# PWR_Stage.net
KiCad netlist of a schematic drawn in Altium Designer
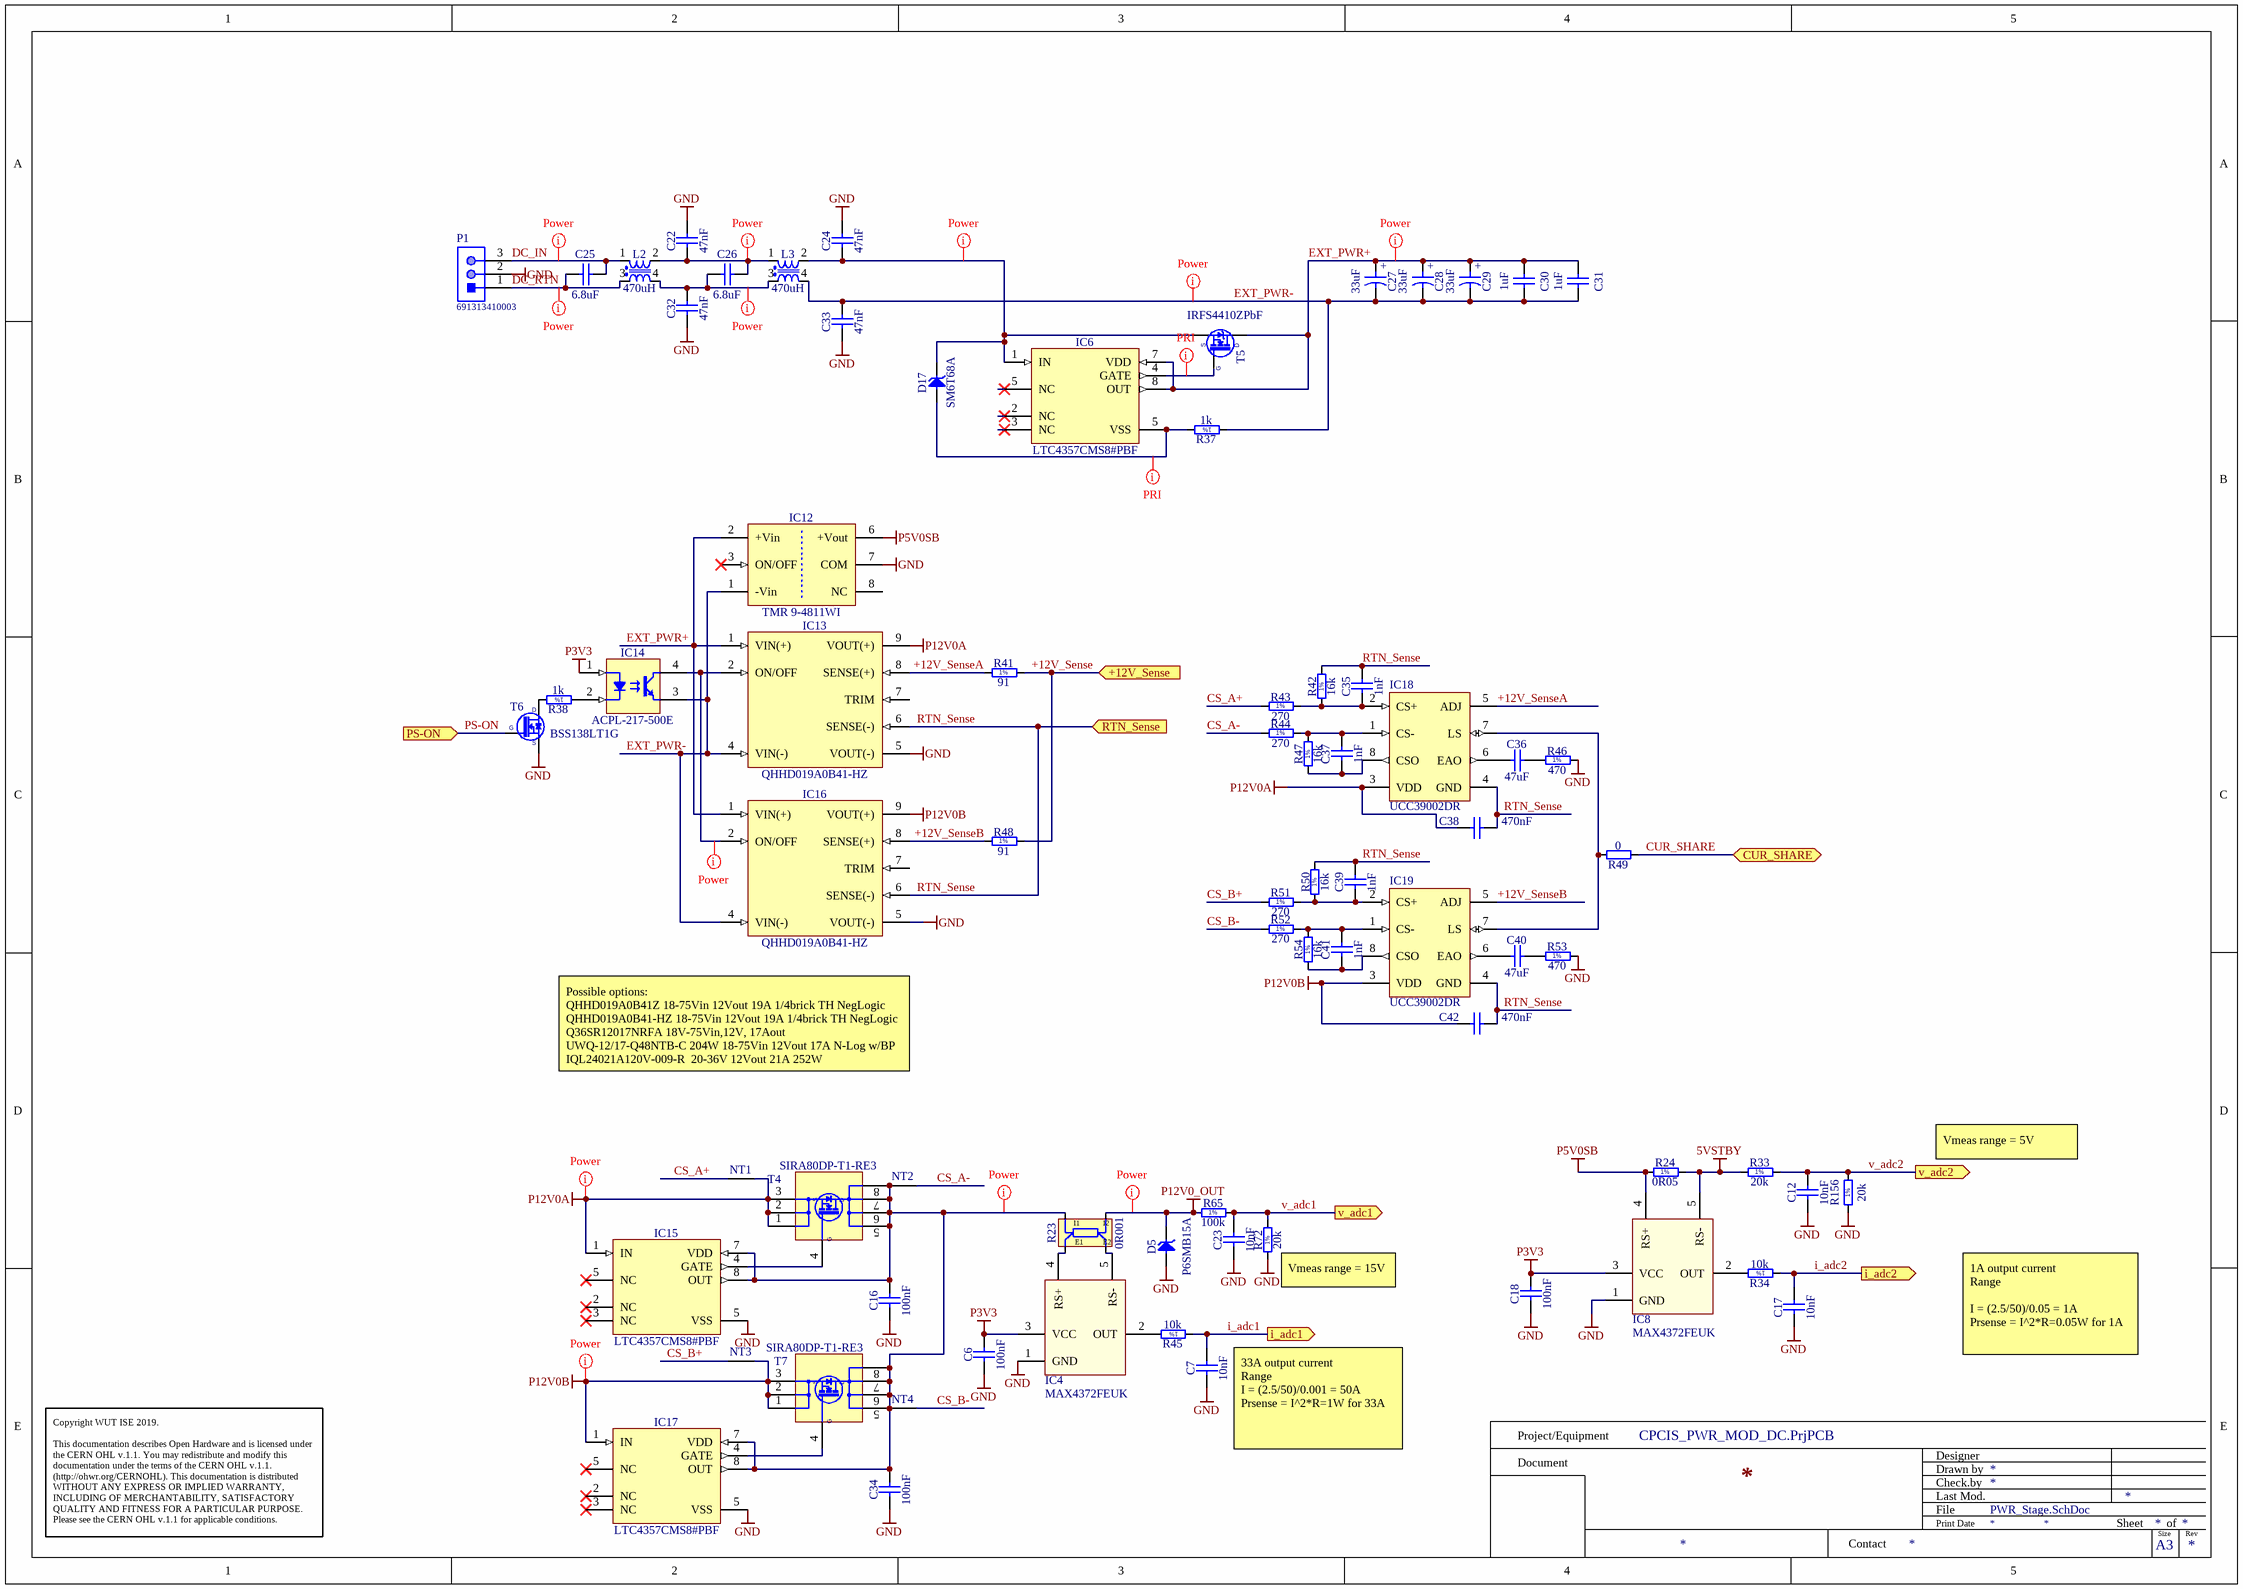
[diagram p0: PWR_Stage.SchDoc]

(export (version "E")
  (design (tool "Eeschema 10.0.6"))
  (components
    (comp (ref "C6")
      (value "100nF")
      (footprint "CAPC1005X55N")
      (description "Non-polarised capacitor")
      (fields
        (field (name "PART NUMBER") "CC0402_100NF_25V_10%_X7R_YUDEN_TMK105B7104KVHF")
        (field (name "VOLTAGE") "25V")
        (field (name "AUTHOR") "CERN DEM JLC")
      )
      (libsource (lib "Capacitors") (part "Capacitor - non polarized"))
    )
    (comp (ref "C7")
      (value "10nF")
      (footprint "CAPC1005X55N")
      (description "Non-polarised capacitor")
      (fields
        (field (name "PART NUMBER") "CC0402_10NF_50V_10%_X7R")
        (field (name "VOLTAGE") "50V")
        (field (name "AUTHOR") "CERN DEM MR")
      )
      (libsource (lib "Capacitors") (part "Capacitor - non polarized"))
    )
    (comp (ref "C12")
      (value "10nF")
      (footprint "CAPC1005X55N")
      (description "Non-polarised capacitor")
      (fields
        (field (name "PART NUMBER") "CC0402_10NF_50V_10%_X7R")
        (field (name "VOLTAGE") "50V")
        (field (name "AUTHOR") "CERN DEM MR")
      )
      (libsource (lib "Capacitors") (part "Capacitor - non polarized"))
    )
    (comp (ref "C16")
      (value "100nF")
      (footprint "CAPC1005X55N")
      (description "Non-polarised capacitor")
      (fields
        (field (name "PART NUMBER") "CC0402_100NF_25V_10%_X7R_YUDEN_TMK105B7104KVHF")
        (field (name "VOLTAGE") "25V")
        (field (name "AUTHOR") "CERN DEM JLC")
      )
      (libsource (lib "Capacitors") (part "Capacitor - non polarized"))
    )
    (comp (ref "C17")
      (value "10nF")
      (footprint "CAPC1005X55N")
      (description "Non-polarised capacitor")
      (fields
        (field (name "PART NUMBER") "CC0402_10NF_50V_10%_X7R")
        (field (name "VOLTAGE") "50V")
        (field (name "AUTHOR") "CERN DEM MR")
      )
      (libsource (lib "Capacitors") (part "Capacitor - non polarized"))
    )
    (comp (ref "C18")
      (value "100nF")
      (footprint "CAPC1005X55N")
      (description "Non-polarised capacitor")
      (fields
        (field (name "PART NUMBER") "CC0402_100NF_25V_10%_X7R_YUDEN_TMK105B7104KVHF")
        (field (name "VOLTAGE") "25V")
        (field (name "AUTHOR") "CERN DEM JLC")
      )
      (libsource (lib "Capacitors") (part "Capacitor - non polarized"))
    )
    (comp (ref "C22")
      (value "47nF")
      (footprint "CAPR1500-500X1800X1050")
      (description "Non-polarised capacitor")
      (fields
        (field (name "PART NUMBER") "CPPR_47NF_630V_5%_1500-500X1800X1050")
        (field (name "VOLTAGE") "630VDC/250VAC")
        (field (name "AUTHOR") "CERN DEM JLC")
      )
      (libsource (lib "Capacitors") (part "Capacitor - non polarized"))
    )
    (comp (ref "C23")
      (value "10nF")
      (footprint "CAPC1005X55N")
      (description "Non-polarised capacitor")
      (fields
        (field (name "PART NUMBER") "CC0402_10NF_50V_10%_X7R")
        (field (name "VOLTAGE") "50V")
        (field (name "AUTHOR") "CERN DEM MR")
      )
      (libsource (lib "Capacitors") (part "Capacitor - non polarized"))
    )
    (comp (ref "C24")
      (value "47nF")
      (footprint "CAPR1500-500X1800X1050")
      (description "Non-polarised capacitor")
      (fields
        (field (name "PART NUMBER") "CPPR_47NF_630V_5%_1500-500X1800X1050")
        (field (name "VOLTAGE") "630VDC/250VAC")
        (field (name "AUTHOR") "CERN DEM JLC")
      )
      (libsource (lib "Capacitors") (part "Capacitor - non polarized"))
    )
    (comp (ref "C25")
      (value "6.8uF")
      (footprint "CAPR2750-1500X3150X2600")
      (description "Non-polarised capacitor")
      (fields
        (field (name "PART NUMBER") "CPPR_6.8UF_100V_20%_2750-1500X3150X2600")
        (field (name "VOLTAGE") "100VDC/63VAC")
        (field (name "AUTHOR") "CERN DEM JLC")
      )
      (libsource (lib "Capacitors") (part "Capacitor - non polarized"))
    )
    (comp (ref "C26")
      (value "6.8uF")
      (footprint "CAPR2750-1500X3150X2600")
      (description "Non-polarised capacitor")
      (fields
        (field (name "PART NUMBER") "CPPR_6.8UF_100V_20%_2750-1500X3150X2600")
        (field (name "VOLTAGE") "100VDC/63VAC")
        (field (name "AUTHOR") "CERN DEM JLC")
      )
      (libsource (lib "Capacitors") (part "Capacitor - non polarized"))
    )
    (comp (ref "C27")
      (value "33uF")
      (footprint "CAPPR500-1050X1350")
      (description "Polarised capacitor")
      (fields
        (field (name "PART NUMBER") "CAER_33UF_100V_20%_PANASONIC_EEUFC2A330")
        (field (name "VOLTAGE") "100V")
        (field (name "AUTHOR") "CERN DEM JLC")
      )
      (libsource (lib "Capacitors") (part "Capacitor - polarized"))
    )
    (comp (ref "C28")
      (value "33uF")
      (footprint "CAPPR500-1050X1350")
      (description "Polarised capacitor")
      (fields
        (field (name "PART NUMBER") "CAER_33UF_100V_20%_PANASONIC_EEUFC2A330")
        (field (name "VOLTAGE") "100V")
        (field (name "AUTHOR") "CERN DEM JLC")
      )
      (libsource (lib "Capacitors") (part "Capacitor - polarized"))
    )
    (comp (ref "C29")
      (value "33uF")
      (footprint "CAPPR500-1050X1350")
      (description "Polarised capacitor")
      (fields
        (field (name "PART NUMBER") "CAER_33UF_100V_20%_PANASONIC_EEUFC2A330")
        (field (name "VOLTAGE") "100V")
        (field (name "AUTHOR") "CERN DEM JLC")
      )
      (libsource (lib "Capacitors") (part "Capacitor - polarized"))
    )
    (comp (ref "C30")
      (value "1uF")
      (footprint "CAPR1000-520X1320X1200")
      (description "Non-polarised capacitor")
      (fields
        (field (name "PART NUMBER") "CPER_1UF_100V_5%_KEMET_R60")
        (field (name "VOLTAGE") "100V")
        (field (name "AUTHOR") "CERN DEM JLC")
      )
      (libsource (lib "Capacitors") (part "Capacitor - non polarized"))
    )
    (comp (ref "C31")
      (value "1uF")
      (footprint "CAPR1000-520X1320X1200")
      (description "Non-polarised capacitor")
      (fields
        (field (name "PART NUMBER") "CPER_1UF_100V_5%_KEMET_R60")
        (field (name "VOLTAGE") "100V")
        (field (name "AUTHOR") "CERN DEM JLC")
      )
      (libsource (lib "Capacitors") (part "Capacitor - non polarized"))
    )
    (comp (ref "C32")
      (value "47nF")
      (footprint "CAPR1500-500X1800X1050")
      (description "Non-polarised capacitor")
      (fields
        (field (name "PART NUMBER") "CPPR_47NF_630V_5%_1500-500X1800X1050")
        (field (name "VOLTAGE") "630VDC/250VAC")
        (field (name "AUTHOR") "CERN DEM JLC")
      )
      (libsource (lib "Capacitors") (part "Capacitor - non polarized"))
    )
    (comp (ref "C33")
      (value "47nF")
      (footprint "CAPR1500-500X1800X1050")
      (description "Non-polarised capacitor")
      (fields
        (field (name "PART NUMBER") "CPPR_47NF_630V_5%_1500-500X1800X1050")
        (field (name "VOLTAGE") "630VDC/250VAC")
        (field (name "AUTHOR") "CERN DEM JLC")
      )
      (libsource (lib "Capacitors") (part "Capacitor - non polarized"))
    )
    (comp (ref "C34")
      (value "100nF")
      (footprint "CAPC1005X55N")
      (description "Non-polarised capacitor")
      (fields
        (field (name "PART NUMBER") "CC0402_100NF_25V_10%_X7R_YUDEN_TMK105B7104KVHF")
        (field (name "VOLTAGE") "25V")
        (field (name "AUTHOR") "CERN DEM JLC")
      )
      (libsource (lib "Capacitors") (part "Capacitor - non polarized"))
    )
    (comp (ref "C35")
      (value "1nF")
      (footprint "CAPC1005X55N")
      (description "Non-polarised capacitor")
      (fields
        (field (name "PART NUMBER") "CC0402_1NF_50V_10%_X7R")
        (field (name "VOLTAGE") "50V")
        (field (name "AUTHOR") "CERN DEM JLC")
      )
      (libsource (lib "Capacitors") (part "Capacitor - non polarized"))
    )
    (comp (ref "C36")
      (value "47uF")
      (footprint "CAPC1608X100N")
      (description "Non-polarised capacitor")
      (fields
        (field (name "PART NUMBER") "CC0603_47UF_6.3V_20%_X5R")
        (field (name "VOLTAGE") "6.3V")
        (field (name "AUTHOR") "CERN DEM JLC")
      )
      (libsource (lib "Capacitors") (part "Capacitor - non polarized"))
    )
    (comp (ref "C37")
      (value "1nF")
      (footprint "CAPC1005X55N")
      (description "Non-polarised capacitor")
      (fields
        (field (name "PART NUMBER") "CC0402_1NF_50V_10%_X7R")
        (field (name "VOLTAGE") "50V")
        (field (name "AUTHOR") "CERN DEM JLC")
      )
      (libsource (lib "Capacitors") (part "Capacitor - non polarized"))
    )
    (comp (ref "C38")
      (value "470nF")
      (footprint "CAPC1608X87N")
      (description "Non-polarised capacitor")
      (fields
        (field (name "PART NUMBER") "CC0603_470NF_50V_10%_X5R")
        (field (name "VOLTAGE") "50V")
        (field (name "AUTHOR") "CERN DEM MR")
      )
      (libsource (lib "Capacitors") (part "Capacitor - non polarized"))
    )
    (comp (ref "C39")
      (value "1nF")
      (footprint "CAPC1005X55N")
      (description "Non-polarised capacitor")
      (fields
        (field (name "PART NUMBER") "CC0402_1NF_50V_10%_X7R")
        (field (name "VOLTAGE") "50V")
        (field (name "AUTHOR") "CERN DEM JLC")
      )
      (libsource (lib "Capacitors") (part "Capacitor - non polarized"))
    )
    (comp (ref "C40")
      (value "47uF")
      (footprint "CAPC1608X100N")
      (description "Non-polarised capacitor")
      (fields
        (field (name "PART NUMBER") "CC0603_47UF_6.3V_20%_X5R")
        (field (name "VOLTAGE") "6.3V")
        (field (name "AUTHOR") "CERN DEM JLC")
      )
      (libsource (lib "Capacitors") (part "Capacitor - non polarized"))
    )
    (comp (ref "C41")
      (value "1nF")
      (footprint "CAPC1005X55N")
      (description "Non-polarised capacitor")
      (fields
        (field (name "PART NUMBER") "CC0402_1NF_50V_10%_X7R")
        (field (name "VOLTAGE") "50V")
        (field (name "AUTHOR") "CERN DEM JLC")
      )
      (libsource (lib "Capacitors") (part "Capacitor - non polarized"))
    )
    (comp (ref "C42")
      (value "470nF")
      (footprint "CAPC1608X87N")
      (description "Non-polarised capacitor")
      (fields
        (field (name "PART NUMBER") "CC0603_470NF_50V_10%_X5R")
        (field (name "VOLTAGE") "50V")
        (field (name "AUTHOR") "CERN DEM MR")
      )
      (libsource (lib "Capacitors") (part "Capacitor - non polarized"))
    )
    (comp (ref "D5")
      (value "P6SMB15A")
      (footprint "DIOM5436X261N")
      (description "Transient Voltage Suppressor Diode (Uni-Directional)")
      (fields
        (field (name "VOLTAGE") "15V")
        (field (name "POWER") "600W")
        (field (name "AUTHOR") "CERN DEM JLC")
      )
      (libsource (lib "ICs And Semiconductors") (part "Diode TVS Uni-Directional"))
    )
    (comp (ref "D17")
      (value "SM6T68A")
      (footprint "DIOM5436X265N")
      (description "Transient Voltage Suppressor Diode (Uni-Directional)")
      (fields
        (field (name "VOLTAGE") "68V")
        (field (name "POWER") "600W")
        (field (name "AUTHOR") "CERN DEM JLC")
      )
      (libsource (lib "ICs And Semiconductors") (part "Diode TVS Uni-Directional"))
    )
    (comp (ref "IC4")
      (value "MAX4372FEUK")
      (footprint "SOT95P270X145-5N")
      (fields (field (name "MANUFACTURER") "Maxim"))
      (libsource (lib "LIBRARY_SCH") (part "PM_MAX4372FEUK"))
    )
    (comp (ref "IC6")
      (value "LTC4357CMS8#PBF")
      (footprint "SOP65P490X110-8N")
      (description "Positive High Voltage Ideal Diode Controller")
      (fields (field (name "MANUFACTURER") "LINEAR TECHNOLOGY") (field (name "AUTHOR") "GK"))
      (libsource (lib "ICs_Analog_Interfaces") (part "LTC4357CMS8#PBF"))
    )
    (comp (ref "IC8")
      (value "MAX4372FEUK")
      (footprint "SOT95P270X145-5N")
      (fields (field (name "MANUFACTURER") "Maxim"))
      (libsource (lib "LIBRARY_SCH") (part "PM_MAX4372FEUK"))
    )
    (comp (ref "IC12")
      (value "TMR 9-4811WI")
      (footprint "DCDC_TRACO_TMR9WI")
      (description "18-75VDC to 5VDC, Iout (max) 1600mA, 9W DC-DC Converter")
      (fields (field (name "MANUFACTURER") "TRACO POWER") (field (name "AUTHOR") "GK"))
      (libsource (lib "Regulators_SMPS") (part "DCDC_TRACO_TMR9WI"))
    )
    (comp (ref "IC13")
      (value "QHHD019A0B41-HZ")
      (footprint "DCDC_quad_brick")
      (description "18 - 75V to 12V 19A, 225W  DC/DC Power Module")
      (fields (field (name "MANUFACTURER") "ABB Power Electronics Inc.") (field (name "AUTHOR") "GK"))
      (libsource (lib "Regulators_SMPS") (part "DCDC_ABB_QHHD019A0B"))
    )
    (comp (ref "IC14")
      (value "ACPL-217-500E")
      (footprint "SOIC127P700X242-4N")
      (description "Single Optocoupler")
      (fields (field (name "MANUFACTURER") "AVAGO TECHNOLOGIES") (field (name "AUTHOR") "CERN DEM JLC"))
      (libsource (lib "ICs And Semiconductors") (part "Optocoupler Type7"))
    )
    (comp (ref "IC15")
      (value "LTC4357CMS8#PBF")
      (footprint "SOP65P490X110-8N")
      (description "Positive High Voltage Ideal Diode Controller")
      (fields (field (name "MANUFACTURER") "LINEAR TECHNOLOGY") (field (name "AUTHOR") "GK"))
      (libsource (lib "ICs_Analog_Interfaces") (part "LTC4357CMS8#PBF"))
    )
    (comp (ref "IC16")
      (value "QHHD019A0B41-HZ")
      (footprint "DCDC_quad_brick")
      (description "18 - 75V to 12V 19A, 225W  DC/DC Power Module")
      (fields (field (name "MANUFACTURER") "ABB Power Electronics Inc.") (field (name "AUTHOR") "GK"))
      (libsource (lib "Regulators_SMPS") (part "DCDC_ABB_QHHD019A0B"))
    )
    (comp (ref "IC17")
      (value "LTC4357CMS8#PBF")
      (footprint "SOP65P490X110-8N")
      (description "Positive High Voltage Ideal Diode Controller")
      (fields (field (name "MANUFACTURER") "LINEAR TECHNOLOGY") (field (name "AUTHOR") "GK"))
      (libsource (lib "ICs_Analog_Interfaces") (part "LTC4357CMS8#PBF"))
    )
    (comp (ref "IC18")
      (value "UCC39002DR")
      (footprint "D0008A_N")
      (fields (field (name "MANUFACTURER") "Texas Instruments"))
      (libsource (lib "Altium Content Vault") (part "TI-UCC39002D8"))
    )
    (comp (ref "IC19")
      (value "UCC39002DR")
      (footprint "D0008A_N")
      (fields (field (name "MANUFACTURER") "Texas Instruments"))
      (libsource (lib "Altium Content Vault") (part "TI-UCC39002D8"))
    )
    (comp (ref "L2")
      (value "470uH")
      (footprint "IND_PULSE_BIG FOOT")
      (description "Inductor Common Mode")
      (fields
        (field (name "PART NUMBER") "IND_470UH_35%_PULSE_P0502NL")
        (field (name "POWER") "14A")
        (field (name "AUTHOR") "CERN DEM JLC")
      )
      (libsource (lib "Inductors & Transformers") (part "Inductor Common Mode 1Dot-2 3Dot-4"))
    )
    (comp (ref "L3")
      (value "470uH")
      (footprint "IND_PULSE_BIG FOOT")
      (description "Inductor Common Mode")
      (fields
        (field (name "PART NUMBER") "IND_470UH_35%_PULSE_P0502NL")
        (field (name "POWER") "14A")
        (field (name "AUTHOR") "CERN DEM JLC")
      )
      (libsource (lib "Inductors & Transformers") (part "Inductor Common Mode 1Dot-2 3Dot-4"))
    )
    (comp (ref "NT1")
      (value "Net Tie")
      (footprint "Net Tie")
      (fields (field (name "AUTHOR") "CERN DEM JLC"))
      (libsource (lib "Eletro-mechanical") (part "Net Tie"))
    )
    (comp (ref "NT2")
      (value "Net Tie")
      (footprint "Net Tie")
      (fields (field (name "AUTHOR") "CERN DEM JLC"))
      (libsource (lib "Eletro-mechanical") (part "Net Tie"))
    )
    (comp (ref "NT3")
      (value "Net Tie")
      (footprint "Net Tie")
      (fields (field (name "AUTHOR") "CERN DEM JLC"))
      (libsource (lib "Eletro-mechanical") (part "Net Tie"))
    )
    (comp (ref "NT4")
      (value "Net Tie")
      (footprint "Net Tie")
      (fields (field (name "AUTHOR") "CERN DEM JLC"))
      (libsource (lib "Eletro-mechanical") (part "Net Tie"))
    )
    (comp (ref "P1")
      (value "691313410003")
      (footprint "691313410003")
      (description "Serie 3134 - 7.62mm Close Horizontal PCB Header WR-TBL, 3 pin")
      (fields (field (name "MANUFACTURER") "Wurth Elektronik") (field (name "PUBLISHER") "WurthElektronik"))
      (libsource (lib "Altium Content Vault") (part "WE-CN-1P-M-R3"))
    )
    (comp (ref "R23")
      (value "0R001")
      (footprint "RES_VISHAY_WSL3637_0R001-0R0019")
      (description "Power and Current Sensing Resistor")
      (fields
        (field (name "PART NUMBER") "R3637_0R001_1%_3W_50PPM_VISHAY_WSL3637")
        (field (name "POWER") "3W")
        (field (name "AUTHOR") "CERN DEM MR")
      )
      (libsource (lib "Resistors") (part "Current Sense Resistor"))
    )
    (comp (ref "R24")
      (value "0R05")
      (footprint "RESC2012X60N")
      (description "Resistor - 1%")
      (fields
        (field (name "PART NUMBER") "R0805_0R05_1%_0.25W_300PPM")
        (field (name "POWER") "0.25W")
        (field (name "AUTHOR") "CERN DEM MR")
      )
      (libsource (lib "Resistors") (part "Resistor - 1%"))
    )
    (comp (ref "R33")
      (value "20k")
      (footprint "RESC1005X40N")
      (description "Resistor - 1%")
      (fields
        (field (name "PART NUMBER") "R0402_20K_1%_0.0625W_100PPM")
        (field (name "POWER") "0.0625W")
        (field (name "AUTHOR") "CERN DEM JLC")
      )
      (libsource (lib "Resistors") (part "Resistor - 1%"))
    )
    (comp (ref "R34")
      (value "10k")
      (footprint "RESC1005X40N")
      (description "Resistor - 1%")
      (fields
        (field (name "PART NUMBER") "R0402_10K_1%_0.0625W_100PPM")
        (field (name "POWER") "0.0625W")
        (field (name "AUTHOR") "CERN DEM JLC")
      )
      (libsource (lib "Resistors") (part "Resistor - 1%"))
    )
    (comp (ref "R37")
      (value "1k")
      (footprint "RESC3216X65N")
      (description "Resistor - 1%")
      (fields
        (field (name "PART NUMBER") "R1206_1K_1%_0.25W_100PPM")
        (field (name "POWER") "0.25W")
        (field (name "AUTHOR") "CERN DEM JLC")
      )
      (libsource (lib "Resistors") (part "Resistor - 1%"))
    )
    (comp (ref "R38")
      (value "1k")
      (footprint "RESC1005X40N")
      (description "Resistor - 1%")
      (fields
        (field (name "PART NUMBER") "R0402_1K_1%_0.0625W_100PPM")
        (field (name "POWER") "0.0625W")
        (field (name "AUTHOR") "CERN DEM JLC")
      )
      (libsource (lib "Resistors") (part "Resistor - 1%"))
    )
    (comp (ref "R41")
      (value "91")
      (footprint "RESC1608X55N")
      (description "Resistor - 1%")
      (fields
        (field (name "PART NUMBER") "R0603_91R_1%_0.1W_100PPM")
        (field (name "POWER") "0.1W")
        (field (name "AUTHOR") "CERN DEM JLC")
      )
      (libsource (lib "Resistors") (part "Resistor - 1%"))
    )
    (comp (ref "R42")
      (value "16k")
      (footprint "RESC1608X55N")
      (description "Resistor - 1%")
      (fields
        (field (name "PART NUMBER") "R0603_16K_1%_0.1W_100PPM")
        (field (name "POWER") "0.1W")
        (field (name "AUTHOR") "CERN DEM JLC")
      )
      (libsource (lib "Resistors") (part "Resistor - 1%"))
    )
    (comp (ref "R43")
      (value "270")
      (footprint "RESC1608X55N")
      (description "Resistor - 1%")
      (fields
        (field (name "PART NUMBER") "R0603_270R_1%_0.1W_100PPM")
        (field (name "POWER") "0.1W")
        (field (name "AUTHOR") "CERN DEM JLC")
      )
      (libsource (lib "Resistors") (part "Resistor - 1%"))
    )
    (comp (ref "R44")
      (value "270")
      (footprint "RESC1608X55N")
      (description "Resistor - 1%")
      (fields
        (field (name "PART NUMBER") "R0603_270R_1%_0.1W_100PPM")
        (field (name "POWER") "0.1W")
        (field (name "AUTHOR") "CERN DEM JLC")
      )
      (libsource (lib "Resistors") (part "Resistor - 1%"))
    )
    (comp (ref "R45")
      (value "10k")
      (footprint "RESC1005X40N")
      (description "Resistor - 1%")
      (fields
        (field (name "PART NUMBER") "R0402_10K_1%_0.0625W_100PPM")
        (field (name "POWER") "0.0625W")
        (field (name "AUTHOR") "CERN DEM JLC")
      )
      (libsource (lib "Resistors") (part "Resistor - 1%"))
    )
    (comp (ref "R46")
      (value "470")
      (footprint "RESC1005X40N")
      (description "Resistor - 1%")
      (fields
        (field (name "PART NUMBER") "R0402_470R_1%_0.0625W_100PPM")
        (field (name "POWER") "0.0625W")
        (field (name "AUTHOR") "CERN DEM JLC")
      )
      (libsource (lib "Resistors") (part "Resistor - 1%"))
    )
    (comp (ref "R47")
      (value "16k")
      (footprint "RESC1608X55N")
      (description "Resistor - 1%")
      (fields
        (field (name "PART NUMBER") "R0603_16K_1%_0.1W_100PPM")
        (field (name "POWER") "0.1W")
        (field (name "AUTHOR") "CERN DEM JLC")
      )
      (libsource (lib "Resistors") (part "Resistor - 1%"))
    )
    (comp (ref "R48")
      (value "91")
      (footprint "RESC1608X55N")
      (description "Resistor - 1%")
      (fields
        (field (name "PART NUMBER") "R0603_91R_1%_0.1W_100PPM")
        (field (name "POWER") "0.1W")
        (field (name "AUTHOR") "CERN DEM JLC")
      )
      (libsource (lib "Resistors") (part "Resistor - 1%"))
    )
    (comp (ref "R49")
      (value "0")
      (footprint "RESC1608X55N")
      (description "Resistor")
      (fields
        (field (name "PART NUMBER") "R0603_0R_JUMPER")
        (field (name "MANUFACTURER") "GENERIC")
        (field (name "AUTHOR") "CERN DEM JLC")
      )
      (libsource (lib "Resistors") (part "Resistor"))
    )
    (comp (ref "R50")
      (value "16k")
      (footprint "RESC1608X55N")
      (description "Resistor - 1%")
      (fields
        (field (name "PART NUMBER") "R0603_16K_1%_0.1W_100PPM")
        (field (name "POWER") "0.1W")
        (field (name "AUTHOR") "CERN DEM JLC")
      )
      (libsource (lib "Resistors") (part "Resistor - 1%"))
    )
    (comp (ref "R51")
      (value "270")
      (footprint "RESC1608X55N")
      (description "Resistor - 1%")
      (fields
        (field (name "PART NUMBER") "R0603_270R_1%_0.1W_100PPM")
        (field (name "POWER") "0.1W")
        (field (name "AUTHOR") "CERN DEM JLC")
      )
      (libsource (lib "Resistors") (part "Resistor - 1%"))
    )
    (comp (ref "R52")
      (value "270")
      (footprint "RESC1608X55N")
      (description "Resistor - 1%")
      (fields
        (field (name "PART NUMBER") "R0603_270R_1%_0.1W_100PPM")
        (field (name "POWER") "0.1W")
        (field (name "AUTHOR") "CERN DEM JLC")
      )
      (libsource (lib "Resistors") (part "Resistor - 1%"))
    )
    (comp (ref "R53")
      (value "470")
      (footprint "RESC1005X40N")
      (description "Resistor - 1%")
      (fields
        (field (name "PART NUMBER") "R0402_470R_1%_0.0625W_100PPM")
        (field (name "POWER") "0.0625W")
        (field (name "AUTHOR") "CERN DEM JLC")
      )
      (libsource (lib "Resistors") (part "Resistor - 1%"))
    )
    (comp (ref "R54")
      (value "16k")
      (footprint "RESC1608X55N")
      (description "Resistor - 1%")
      (fields
        (field (name "PART NUMBER") "R0603_16K_1%_0.1W_100PPM")
        (field (name "POWER") "0.1W")
        (field (name "AUTHOR") "CERN DEM JLC")
      )
      (libsource (lib "Resistors") (part "Resistor - 1%"))
    )
    (comp (ref "R65")
      (value "100k")
      (footprint "RESC1005X40N")
      (description "Resistor - 1%")
      (fields
        (field (name "PART NUMBER") "R0402_100K_1%_0.0625W_100PPM")
        (field (name "POWER") "0.0625W")
        (field (name "AUTHOR") "CERN DEM JLC")
      )
      (libsource (lib "Resistors") (part "Resistor - 1%"))
    )
    (comp (ref "R72")
      (value "20k")
      (footprint "RESC1005X40N")
      (description "Resistor - 1%")
      (fields
        (field (name "PART NUMBER") "R0402_20K_1%_0.0625W_100PPM")
        (field (name "POWER") "0.0625W")
        (field (name "AUTHOR") "CERN DEM JLC")
      )
      (libsource (lib "Resistors") (part "Resistor - 1%"))
    )
    (comp (ref "R156")
      (value "20k")
      (footprint "RESC1005X40N")
      (description "Resistor - 1%")
      (fields
        (field (name "PART NUMBER") "R0402_20K_1%_0.0625W_100PPM")
        (field (name "POWER") "0.0625W")
        (field (name "AUTHOR") "CERN DEM JLC")
      )
      (libsource (lib "Resistors") (part "Resistor - 1%"))
    )
    (comp (ref "T4")
      (value "SIRA80DP-T1-RE3")
      (footprint "VISHAY_POWERPAK-SO-8-SINGLE")
      (description "100A N-Channel 30-V (D-S) MOSFET")
      (fields
        (field (name "PART NUMBER") "SI7898DP-T1-E3")
        (field (name "MANUFACTURER") "VISHAY SILICONIX")
        (field (name "AUTHOR") "GK")
      )
      (libsource (lib "Tranistors_Thyristors") (part "Q_SIRA80DP-T1-RE3"))
    )
    (comp (ref "T5")
      (value "IRFS4410ZPbF")
      (footprint "TO254P1524X483-3N-R1067X686")
      (description "N-CHANNEL MOSFET WITH ZENER DIODE")
      (fields (field (name "MANUFACTURER") "INTERNATIONAL RECTIFIER") (field (name "AUTHOR") "CERN DEM JMW"))
      (libsource (lib "ICs And Semiconductors") (part "N-MOSFET-DZ 1G 2S 3D"))
    )
    (comp (ref "T6")
      (value "BSS138LT1G")
      (footprint "SOT95P240X110-3N")
      (description "N-CHANNEL MOSFET WITH DIODE")
      (fields (field (name "MANUFACTURER") "ON SEMICONDUCTOR") (field (name "AUTHOR") "CERN DEM JLC"))
      (libsource (lib "ICs And Semiconductors") (part "N-MOSFET-D 1G 2S 3D"))
    )
    (comp (ref "T7")
      (value "SIRA80DP-T1-RE3")
      (footprint "VISHAY_POWERPAK-SO-8-SINGLE")
      (description "100A N-Channel 30-V (D-S) MOSFET")
      (fields
        (field (name "PART NUMBER") "SI7898DP-T1-E3")
        (field (name "MANUFACTURER") "VISHAY SILICONIX")
        (field (name "AUTHOR") "GK")
      )
      (libsource (lib "Tranistors_Thyristors") (part "Q_SIRA80DP-T1-RE3"))
    )
  )
  (nets
    (net (code "1") (name "/+12V_Sense") (class "Default")
      (node (ref "R41") (pin "2") (pinfunction "2_2") (pintype "passive"))
      (node (ref "R48") (pin "2") (pinfunction "2_2") (pintype "passive"))
    )
    (net (code "2") (name "/+12V_SenseA") (class "Default")
      (node (ref "IC13") (pin "8") (pinfunction "SENSE(+)_8") (pintype "input"))
      (node (ref "IC18") (pin "5") (pinfunction "ADJ_5") (pintype "power_in"))
      (node (ref "R41") (pin "1") (pinfunction "1_1") (pintype "passive"))
    )
    (net (code "3") (name "/+12V_SenseB") (class "Default")
      (node (ref "IC16") (pin "8") (pinfunction "SENSE(+)_8") (pintype "input"))
      (node (ref "IC19") (pin "5") (pinfunction "ADJ_5") (pintype "power_in"))
      (node (ref "R48") (pin "1") (pinfunction "1_1") (pintype "passive"))
    )
    (net (code "4") (name "/CS_A+") (class "Default")
      (node (ref "NT1") (pin "1") (pinfunction "1_1") (pintype "bidirectional"))
      (node (ref "R43") (pin "1") (pinfunction "1_1") (pintype "passive"))
    )
    (net (code "5") (name "/CS_A-") (class "Default")
      (node (ref "NT2") (pin "2") (pinfunction "2_2") (pintype "bidirectional"))
      (node (ref "R44") (pin "1") (pinfunction "1_1") (pintype "passive"))
    )
    (net (code "6") (name "/CS_B+") (class "Default")
      (node (ref "NT3") (pin "1") (pinfunction "1_1") (pintype "bidirectional"))
      (node (ref "R51") (pin "1") (pinfunction "1_1") (pintype "passive"))
    )
    (net (code "7") (name "/CS_B-") (class "Default")
      (node (ref "NT4") (pin "2") (pinfunction "2_2") (pintype "bidirectional"))
      (node (ref "R52") (pin "1") (pinfunction "1_1") (pintype "passive"))
    )
    (net (code "8") (name "/CUR_SHARE") (class "Default")
      (node (ref "R49") (pin "1") (pinfunction "1_1") (pintype "passive"))
    )
    (net (code "9") (name "/DC_IN") (class "Default")
      (node (ref "C25") (pin "2") (pinfunction "2_2") (pintype "passive"))
      (node (ref "L2") (pin "1") (pinfunction "1_1") (pintype "passive"))
      (node (ref "P1") (pin "3") (pinfunction "3_3") (pintype "passive"))
    )
    (net (code "10") (name "/DC_RTN") (class "Default")
      (node (ref "C25") (pin "1") (pinfunction "1_1") (pintype "passive"))
      (node (ref "L2") (pin "3") (pinfunction "3_3") (pintype "passive"))
      (node (ref "P1") (pin "1") (pinfunction "1_1") (pintype "passive"))
    )
    (net (code "11") (name "/EXT_PWR+") (class "Default")
      (node (ref "C27") (pin "1") (pinfunction "1_1") (pintype "passive"))
      (node (ref "C28") (pin "1") (pinfunction "1_1") (pintype "passive"))
      (node (ref "C29") (pin "1") (pinfunction "1_1") (pintype "passive"))
      (node (ref "C30") (pin "1") (pinfunction "1_1") (pintype "passive"))
      (node (ref "C31") (pin "1") (pinfunction "1_1") (pintype "passive"))
      (node (ref "IC12") (pin "2") (pinfunction "+Vin_2") (pintype "power_in"))
      (node (ref "IC13") (pin "1") (pinfunction "VIN(+)_1") (pintype "input"))
      (node (ref "IC16") (pin "1") (pinfunction "VIN(+)_1") (pintype "input"))
      (node (ref "IC6") (pin "7") (pinfunction "VDD_7") (pintype "input"))
      (node (ref "IC6") (pin "8") (pinfunction "OUT_8") (pintype "output"))
      (node (ref "T5") (pin "3") (pinfunction "D_3") (pintype "passive"))
    )
    (net (code "12") (name "/EXT_PWR-") (class "Default")
      (node (ref "C27") (pin "2") (pinfunction "2_2") (pintype "passive"))
      (node (ref "C28") (pin "2") (pinfunction "2_2") (pintype "passive"))
      (node (ref "C29") (pin "2") (pinfunction "2_2") (pintype "passive"))
      (node (ref "C30") (pin "2") (pinfunction "2_2") (pintype "passive"))
      (node (ref "C31") (pin "2") (pinfunction "2_2") (pintype "passive"))
      (node (ref "C33") (pin "2") (pinfunction "2_2") (pintype "passive"))
      (node (ref "IC12") (pin "1") (pinfunction "-Vin_1") (pintype "power_in"))
      (node (ref "IC13") (pin "4") (pinfunction "VIN(-)_4") (pintype "input"))
      (node (ref "IC14") (pin "3") (pinfunction "E_3") (pintype "open_emitter"))
      (node (ref "IC16") (pin "4") (pinfunction "VIN(-)_4") (pintype "input"))
      (node (ref "L3") (pin "4") (pinfunction "4_4") (pintype "passive"))
      (node (ref "R37") (pin "1") (pinfunction "1_1") (pintype "passive"))
    )
    (net (code "13") (name "/PS-ON") (class "Default")
      (node (ref "T6") (pin "1") (pinfunction "G_1") (pintype "passive"))
    )
    (net (code "14") (name "/RTN_Sense") (class "Default")
      (node (ref "C35") (pin "2") (pinfunction "2_2") (pintype "passive"))
      (node (ref "C38") (pin "1") (pinfunction "1_1") (pintype "passive"))
      (node (ref "C39") (pin "2") (pinfunction "2_2") (pintype "passive"))
      (node (ref "C42") (pin "1") (pinfunction "1_1") (pintype "passive"))
      (node (ref "IC13") (pin "6") (pinfunction "SENSE(-)_6") (pintype "input"))
      (node (ref "IC16") (pin "6") (pinfunction "SENSE(-)_6") (pintype "input"))
      (node (ref "IC18") (pin "4") (pinfunction "GND_4") (pintype "power_in"))
      (node (ref "IC19") (pin "4") (pinfunction "GND_4") (pintype "power_in"))
      (node (ref "R42") (pin "2") (pinfunction "2_2") (pintype "passive"))
      (node (ref "R50") (pin "2") (pinfunction "2_2") (pintype "passive"))
    )
    (net (code "15") (name "/i_adc1") (class "Default")
      (node (ref "C7") (pin "2") (pinfunction "2_2") (pintype "passive"))
      (node (ref "R45") (pin "1") (pinfunction "1_1") (pintype "passive"))
    )
    (net (code "16") (name "/i_adc2") (class "Default")
      (node (ref "C17") (pin "2") (pinfunction "2_2") (pintype "passive"))
      (node (ref "R34") (pin "1") (pinfunction "1_1") (pintype "passive"))
    )
    (net (code "17") (name "/v_adc1") (class "Default")
      (node (ref "C23") (pin "2") (pinfunction "2_2") (pintype "passive"))
      (node (ref "R65") (pin "2") (pinfunction "2_2") (pintype "passive"))
      (node (ref "R72") (pin "2") (pinfunction "2_2") (pintype "passive"))
    )
    (net (code "18") (name "/v_adc2") (class "Default")
      (node (ref "C12") (pin "2") (pinfunction "2_2") (pintype "passive"))
      (node (ref "R156") (pin "2") (pinfunction "2_2") (pintype "passive"))
      (node (ref "R33") (pin "2") (pinfunction "2_2") (pintype "passive"))
    )
    (net (code "19") (name "5VSTBY") (class "Default")
      (node (ref "IC8") (pin "5") (pinfunction "RS-_5") (pintype "passive"))
      (node (ref "R24") (pin "2") (pinfunction "2_2") (pintype "passive"))
      (node (ref "R33") (pin "1") (pinfunction "1_1") (pintype "passive"))
    )
    (net (code "20") (name "GND") (class "Default")
      (node (ref "C12") (pin "1") (pinfunction "1_1") (pintype "passive"))
      (node (ref "C16") (pin "1") (pinfunction "1_1") (pintype "passive"))
      (node (ref "C17") (pin "1") (pinfunction "1_1") (pintype "passive"))
      (node (ref "C18") (pin "1") (pinfunction "1_1") (pintype "passive"))
      (node (ref "C22") (pin "2") (pinfunction "2_2") (pintype "passive"))
      (node (ref "C23") (pin "1") (pinfunction "1_1") (pintype "passive"))
      (node (ref "C24") (pin "2") (pinfunction "2_2") (pintype "passive"))
      (node (ref "C32") (pin "1") (pinfunction "1_1") (pintype "passive"))
      (node (ref "C33") (pin "1") (pinfunction "1_1") (pintype "passive"))
      (node (ref "C34") (pin "1") (pinfunction "1_1") (pintype "passive"))
      (node (ref "C6") (pin "1") (pinfunction "1_1") (pintype "passive"))
      (node (ref "C7") (pin "1") (pinfunction "1_1") (pintype "passive"))
      (node (ref "D5") (pin "2") (pinfunction "A_2") (pintype "passive"))
      (node (ref "IC12") (pin "7") (pinfunction "COM_7") (pintype "power_in"))
      (node (ref "IC13") (pin "5") (pinfunction "VOUT(-)_5") (pintype "power_in"))
      (node (ref "IC15") (pin "5") (pinfunction "VSS_5") (pintype "power_in"))
      (node (ref "IC16") (pin "5") (pinfunction "VOUT(-)_5") (pintype "power_in"))
      (node (ref "IC17") (pin "5") (pinfunction "VSS_5") (pintype "power_in"))
      (node (ref "IC4") (pin "1") (pinfunction "GND_1") (pintype "passive"))
      (node (ref "IC8") (pin "1") (pinfunction "GND_1") (pintype "passive"))
      (node (ref "P1") (pin "2") (pinfunction "2_2") (pintype "passive"))
      (node (ref "R156") (pin "1") (pinfunction "1_1") (pintype "passive"))
      (node (ref "R46") (pin "2") (pinfunction "2_2") (pintype "passive"))
      (node (ref "R53") (pin "2") (pinfunction "2_2") (pintype "passive"))
      (node (ref "R72") (pin "1") (pinfunction "1_1") (pintype "passive"))
      (node (ref "T6") (pin "2") (pinfunction "S_2") (pintype "passive"))
    )
    (net (code "21") (name "Net-(C22-Pad1)") (class "Default")
      (node (ref "C22") (pin "1") (pinfunction "1_1") (pintype "passive"))
      (node (ref "C26") (pin "2") (pinfunction "2_2") (pintype "passive"))
      (node (ref "L2") (pin "2") (pinfunction "2_2") (pintype "passive"))
      (node (ref "L3") (pin "1") (pinfunction "1_1") (pintype "passive"))
    )
    (net (code "22") (name "Net-(C26-Pad1)") (class "Default")
      (node (ref "C26") (pin "1") (pinfunction "1_1") (pintype "passive"))
      (node (ref "C32") (pin "2") (pinfunction "2_2") (pintype "passive"))
      (node (ref "L2") (pin "4") (pinfunction "4_4") (pintype "passive"))
      (node (ref "L3") (pin "3") (pinfunction "3_3") (pintype "passive"))
    )
    (net (code "23") (name "Net-(C36-Pad2)") (class "Default")
      (node (ref "C36") (pin "2") (pinfunction "2_2") (pintype "passive"))
      (node (ref "R46") (pin "1") (pinfunction "1_1") (pintype "passive"))
    )
    (net (code "24") (name "Net-(C40-Pad2)") (class "Default")
      (node (ref "C40") (pin "2") (pinfunction "2_2") (pintype "passive"))
      (node (ref "R53") (pin "1") (pinfunction "1_1") (pintype "passive"))
    )
    (net (code "25") (name "Net-(D17-A)") (class "Default")
      (node (ref "D17") (pin "2") (pinfunction "A_2") (pintype "passive"))
      (node (ref "IC6") (pin "5") (pinfunction "VSS_5") (pintype "power_in"))
      (node (ref "R37") (pin "2") (pinfunction "2_2") (pintype "passive"))
    )
    (net (code "26") (name "Net-(D17-C)") (class "Default")
      (node (ref "C24") (pin "1") (pinfunction "1_1") (pintype "passive"))
      (node (ref "D17") (pin "1") (pinfunction "C_1") (pintype "passive"))
      (node (ref "IC6") (pin "1") (pinfunction "IN_1") (pintype "input"))
      (node (ref "L3") (pin "2") (pinfunction "2_2") (pintype "passive"))
      (node (ref "T5") (pin "2") (pinfunction "S_2") (pintype "passive"))
    )
    (net (code "27") (name "Net-(IC4-OUT)") (class "Default")
      (node (ref "IC4") (pin "2") (pinfunction "OUT_2") (pintype "passive"))
      (node (ref "R45") (pin "2") (pinfunction "2_2") (pintype "passive"))
    )
    (net (code "28") (name "Net-(IC4-RS+)") (class "Default")
      (node (ref "IC4") (pin "4") (pinfunction "RS+_4") (pintype "passive"))
      (node (ref "R23") (pin "E1") (pinfunction "E1_E1") (pintype "passive"))
    )
    (net (code "29") (name "Net-(IC4-RS-)") (class "Default")
      (node (ref "IC4") (pin "5") (pinfunction "RS-_5") (pintype "passive"))
      (node (ref "R23") (pin "E2") (pinfunction "E2_E2") (pintype "passive"))
    )
    (net (code "30") (name "Net-(IC6-GATE)") (class "Default")
      (node (ref "IC6") (pin "4") (pinfunction "GATE_4") (pintype "output"))
      (node (ref "T5") (pin "1") (pinfunction "G_1") (pintype "passive"))
    )
    (net (code "31") (name "Net-(IC8-OUT)") (class "Default")
      (node (ref "IC8") (pin "2") (pinfunction "OUT_2") (pintype "passive"))
      (node (ref "R34") (pin "2") (pinfunction "2_2") (pintype "passive"))
    )
    (net (code "32") (name "Net-(IC13-ON{slash}OFF)") (class "Default")
      (node (ref "IC13") (pin "2") (pinfunction "ON/OFF_2") (pintype "input"))
      (node (ref "IC14") (pin "4") (pinfunction "C_4") (pintype "open_collector"))
      (node (ref "IC16") (pin "2") (pinfunction "ON/OFF_2") (pintype "input"))
    )
    (net (code "33") (name "Net-(IC14-C-Pad2)") (class "Default")
      (node (ref "IC14") (pin "2") (pinfunction "C_2") (pintype "input"))
      (node (ref "R38") (pin "1") (pinfunction "1_1") (pintype "passive"))
    )
    (net (code "34") (name "Net-(IC15-GATE)") (class "Default")
      (node (ref "IC15") (pin "4") (pinfunction "GATE_4") (pintype "output"))
      (node (ref "T4") (pin "4") (pinfunction "S_4") (pintype "passive"))
    )
    (net (code "35") (name "Net-(IC15-OUT)") (class "Default")
      (node (ref "C16") (pin "2") (pinfunction "2_2") (pintype "passive"))
      (node (ref "C34") (pin "2") (pinfunction "2_2") (pintype "passive"))
      (node (ref "IC15") (pin "7") (pinfunction "VDD_7") (pintype "input"))
      (node (ref "IC15") (pin "8") (pinfunction "OUT_8") (pintype "output"))
      (node (ref "IC17") (pin "7") (pinfunction "VDD_7") (pintype "input"))
      (node (ref "IC17") (pin "8") (pinfunction "OUT_8") (pintype "output"))
      (node (ref "NT2") (pin "1") (pinfunction "1_1") (pintype "bidirectional"))
      (node (ref "NT4") (pin "1") (pinfunction "1_1") (pintype "bidirectional"))
      (node (ref "R23") (pin "I1") (pinfunction "I1_I1") (pintype "passive"))
      (node (ref "T4") (pin "D") (pinfunction "D_D") (pintype "passive"))
      (node (ref "T7") (pin "D") (pinfunction "D_D") (pintype "passive"))
    )
    (net (code "36") (name "Net-(IC17-GATE)") (class "Default")
      (node (ref "IC17") (pin "4") (pinfunction "GATE_4") (pintype "output"))
      (node (ref "T7") (pin "4") (pinfunction "S_4") (pintype "passive"))
    )
    (net (code "37") (name "Net-(IC18-CS+)") (class "Default")
      (node (ref "C35") (pin "1") (pinfunction "1_1") (pintype "passive"))
      (node (ref "IC18") (pin "2") (pinfunction "CS+_2") (pintype "input"))
      (node (ref "R42") (pin "1") (pinfunction "1_1") (pintype "passive"))
      (node (ref "R43") (pin "2") (pinfunction "2_2") (pintype "passive"))
    )
    (net (code "38") (name "Net-(IC18-CS-)") (class "Default")
      (node (ref "C37") (pin "2") (pinfunction "2_2") (pintype "passive"))
      (node (ref "IC18") (pin "1") (pinfunction "CS-_1") (pintype "input"))
      (node (ref "R44") (pin "2") (pinfunction "2_2") (pintype "passive"))
      (node (ref "R47") (pin "2") (pinfunction "2_2") (pintype "passive"))
    )
    (net (code "39") (name "Net-(IC18-CSO)") (class "Default")
      (node (ref "C37") (pin "1") (pinfunction "1_1") (pintype "passive"))
      (node (ref "IC18") (pin "8") (pinfunction "CSO_8") (pintype "output"))
      (node (ref "R47") (pin "1") (pinfunction "1_1") (pintype "passive"))
    )
    (net (code "40") (name "Net-(IC18-EAO)") (class "Default")
      (node (ref "C36") (pin "1") (pinfunction "1_1") (pintype "passive"))
      (node (ref "IC18") (pin "6") (pinfunction "EAO_6") (pintype "output"))
    )
    (net (code "41") (name "Net-(IC18-LS)") (class "Default")
      (node (ref "IC18") (pin "7") (pinfunction "LS_7") (pintype "bidirectional"))
      (node (ref "IC19") (pin "7") (pinfunction "LS_7") (pintype "bidirectional"))
      (node (ref "R49") (pin "2") (pinfunction "2_2") (pintype "passive"))
    )
    (net (code "42") (name "Net-(IC19-CS+)") (class "Default")
      (node (ref "C39") (pin "1") (pinfunction "1_1") (pintype "passive"))
      (node (ref "IC19") (pin "2") (pinfunction "CS+_2") (pintype "input"))
      (node (ref "R50") (pin "1") (pinfunction "1_1") (pintype "passive"))
      (node (ref "R51") (pin "2") (pinfunction "2_2") (pintype "passive"))
    )
    (net (code "43") (name "Net-(IC19-CS-)") (class "Default")
      (node (ref "C41") (pin "2") (pinfunction "2_2") (pintype "passive"))
      (node (ref "IC19") (pin "1") (pinfunction "CS-_1") (pintype "input"))
      (node (ref "R52") (pin "2") (pinfunction "2_2") (pintype "passive"))
      (node (ref "R54") (pin "2") (pinfunction "2_2") (pintype "passive"))
    )
    (net (code "44") (name "Net-(IC19-CSO)") (class "Default")
      (node (ref "C41") (pin "1") (pinfunction "1_1") (pintype "passive"))
      (node (ref "IC19") (pin "8") (pinfunction "CSO_8") (pintype "output"))
      (node (ref "R54") (pin "1") (pinfunction "1_1") (pintype "passive"))
    )
    (net (code "45") (name "Net-(IC19-EAO)") (class "Default")
      (node (ref "C40") (pin "1") (pinfunction "1_1") (pintype "passive"))
      (node (ref "IC19") (pin "6") (pinfunction "EAO_6") (pintype "output"))
    )
    (net (code "46") (name "Net-(T6-D)") (class "Default")
      (node (ref "R38") (pin "2") (pinfunction "2_2") (pintype "passive"))
      (node (ref "T6") (pin "3") (pinfunction "D_3") (pintype "passive"))
    )
    (net (code "47") (name "P3V3") (class "Default")
      (node (ref "C18") (pin "2") (pinfunction "2_2") (pintype "passive"))
      (node (ref "C6") (pin "2") (pinfunction "2_2") (pintype "passive"))
      (node (ref "IC14") (pin "1") (pinfunction "A_1") (pintype "input"))
      (node (ref "IC4") (pin "3") (pinfunction "VCC_3") (pintype "passive"))
      (node (ref "IC8") (pin "3") (pinfunction "VCC_3") (pintype "passive"))
    )
    (net (code "48") (name "P5V0SB") (class "Default")
      (node (ref "IC12") (pin "6") (pinfunction "+Vout_6") (pintype "power_in"))
      (node (ref "IC8") (pin "4") (pinfunction "RS+_4") (pintype "passive"))
      (node (ref "R24") (pin "1") (pinfunction "1_1") (pintype "passive"))
    )
    (net (code "49") (name "P12V0A") (class "Default")
      (node (ref "C38") (pin "2") (pinfunction "2_2") (pintype "passive"))
      (node (ref "IC13") (pin "9") (pinfunction "VOUT(+)_9") (pintype "power_in"))
      (node (ref "IC15") (pin "1") (pinfunction "IN_1") (pintype "input"))
      (node (ref "IC18") (pin "3") (pinfunction "VDD_3") (pintype "power_in"))
      (node (ref "NT1") (pin "2") (pinfunction "2_2") (pintype "bidirectional"))
      (node (ref "T4") (pin "1") (pinfunction "S_1") (pintype "passive"))
      (node (ref "T4") (pin "2") (pinfunction "S_2") (pintype "passive"))
      (node (ref "T4") (pin "3") (pinfunction "S_3") (pintype "passive"))
    )
    (net (code "50") (name "P12V0B") (class "Default")
      (node (ref "C42") (pin "2") (pinfunction "2_2") (pintype "passive"))
      (node (ref "IC16") (pin "9") (pinfunction "VOUT(+)_9") (pintype "power_in"))
      (node (ref "IC17") (pin "1") (pinfunction "IN_1") (pintype "input"))
      (node (ref "IC19") (pin "3") (pinfunction "VDD_3") (pintype "power_in"))
      (node (ref "NT3") (pin "2") (pinfunction "2_2") (pintype "bidirectional"))
      (node (ref "T7") (pin "1") (pinfunction "S_1") (pintype "passive"))
      (node (ref "T7") (pin "2") (pinfunction "S_2") (pintype "passive"))
      (node (ref "T7") (pin "3") (pinfunction "S_3") (pintype "passive"))
    )
    (net (code "51") (name "P12V0_OUT") (class "Default")
      (node (ref "D5") (pin "1") (pinfunction "C_1") (pintype "passive"))
      (node (ref "R23") (pin "I2") (pinfunction "I2_I2") (pintype "passive"))
      (node (ref "R65") (pin "1") (pinfunction "1_1") (pintype "passive"))
    )
    (net (code "52") (name "unconnected-(IC6-NC-Pad2)") (class "Default")
      (node (ref "IC6") (pin "2") (pinfunction "NC_2") (pintype "passive+no_connect"))
    )
    (net (code "53") (name "unconnected-(IC6-NC-Pad3)") (class "Default")
      (node (ref "IC6") (pin "3") (pinfunction "NC_3") (pintype "passive+no_connect"))
    )
    (net (code "54") (name "unconnected-(IC6-NC-Pad5)") (class "Default")
      (node (ref "IC6") (pin "5") (pinfunction "NC_5") (pintype "passive+no_connect"))
    )
    (net (code "55") (name "unconnected-(IC12-NC-Pad8)") (class "Default")
      (node (ref "IC12") (pin "8") (pinfunction "NC_8") (pintype "passive"))
    )
    (net (code "56") (name "unconnected-(IC12-ON{slash}OFF-Pad3)") (class "Default")
      (node (ref "IC12") (pin "3") (pinfunction "ON/OFF_3") (pintype "input+no_connect"))
    )
    (net (code "57") (name "unconnected-(IC13-TRIM-Pad7)") (class "Default")
      (node (ref "IC13") (pin "7") (pinfunction "TRIM_7") (pintype "input"))
    )
    (net (code "58") (name "unconnected-(IC15-NC-Pad2)") (class "Default")
      (node (ref "IC15") (pin "2") (pinfunction "NC_2") (pintype "passive+no_connect"))
    )
    (net (code "59") (name "unconnected-(IC15-NC-Pad3)") (class "Default")
      (node (ref "IC15") (pin "3") (pinfunction "NC_3") (pintype "passive+no_connect"))
    )
    (net (code "60") (name "unconnected-(IC15-NC-Pad5)") (class "Default")
      (node (ref "IC15") (pin "5") (pinfunction "NC_5") (pintype "passive+no_connect"))
    )
    (net (code "61") (name "unconnected-(IC16-TRIM-Pad7)") (class "Default")
      (node (ref "IC16") (pin "7") (pinfunction "TRIM_7") (pintype "input"))
    )
    (net (code "62") (name "unconnected-(IC17-NC-Pad2)") (class "Default")
      (node (ref "IC17") (pin "2") (pinfunction "NC_2") (pintype "passive+no_connect"))
    )
    (net (code "63") (name "unconnected-(IC17-NC-Pad3)") (class "Default")
      (node (ref "IC17") (pin "3") (pinfunction "NC_3") (pintype "passive+no_connect"))
    )
    (net (code "64") (name "unconnected-(IC17-NC-Pad5)") (class "Default")
      (node (ref "IC17") (pin "5") (pinfunction "NC_5") (pintype "passive+no_connect"))
    )
  )
)
